# winderController02.net
KiCad netlist of a schematic drawn in EAGLE
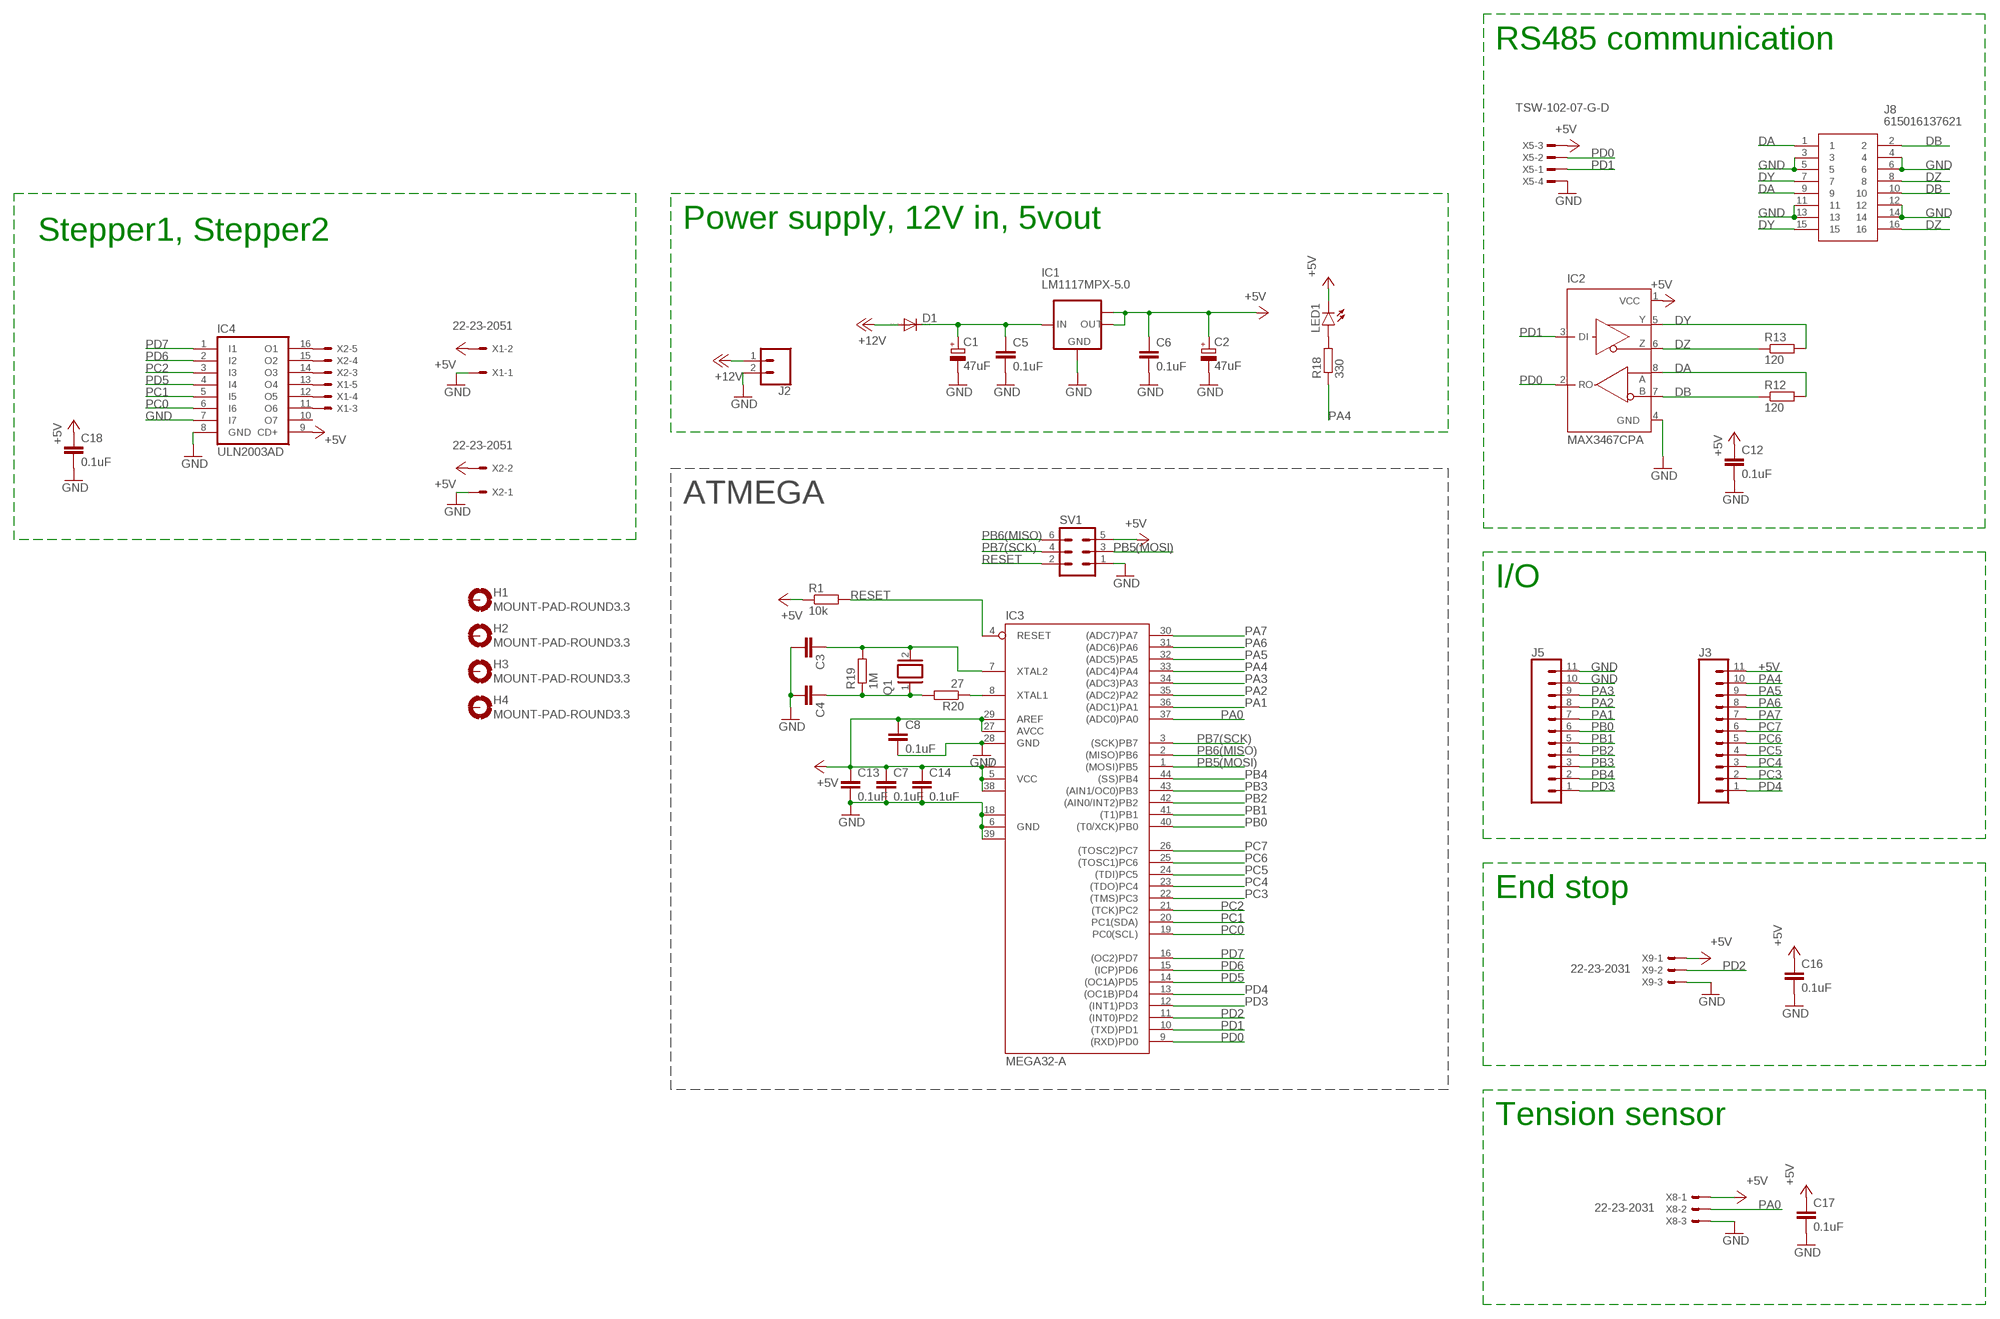
[diagram p0: schematic, sheet 1]

(export (version "E")
  (design (tool "Eeschema 10.0.6"))
  (components
    (comp (ref "C1")
      (value "47uF")
      (footprint "eagle-import:PANASONIC_D")
      (libsource (lib "eagle-import") (part "CPOL-EUD"))
    )
    (comp (ref "C2")
      (value "47uF")
      (footprint "eagle-import:PANASONIC_D")
      (libsource (lib "eagle-import") (part "CPOL-EUD"))
    )
    (comp (ref "C3")
      (value "C-EUC0603")
      (footprint "eagle-import:C0603")
      (libsource (lib "eagle-import") (part "C-EUC0603"))
    )
    (comp (ref "C4")
      (value "C-EUC0603")
      (footprint "eagle-import:C0603")
      (libsource (lib "eagle-import") (part "C-EUC0603"))
    )
    (comp (ref "C5")
      (value "0.1uF")
      (footprint "eagle-import:C0603")
      (libsource (lib "eagle-import") (part "C-EUC0603"))
    )
    (comp (ref "C6")
      (value "0.1uF")
      (footprint "eagle-import:C0603")
      (libsource (lib "eagle-import") (part "C-EUC0603"))
    )
    (comp (ref "C7")
      (value "0.1uF")
      (footprint "eagle-import:C0603")
      (libsource (lib "eagle-import") (part "C-EUC0603"))
    )
    (comp (ref "C8")
      (value "0.1uF")
      (footprint "eagle-import:C0603")
      (libsource (lib "eagle-import") (part "C-EUC0603"))
    )
    (comp (ref "C12")
      (value "0.1uF")
      (footprint "eagle-import:C0603")
      (libsource (lib "eagle-import") (part "C-EUC0603"))
    )
    (comp (ref "C13")
      (value "0.1uF")
      (footprint "eagle-import:C0603")
      (libsource (lib "eagle-import") (part "C-EUC0603"))
    )
    (comp (ref "C14")
      (value "0.1uF")
      (footprint "eagle-import:C0603")
      (libsource (lib "eagle-import") (part "C-EUC0603"))
    )
    (comp (ref "C16")
      (value "0.1uF")
      (footprint "eagle-import:C0603")
      (libsource (lib "eagle-import") (part "C-EUC0603"))
    )
    (comp (ref "C17")
      (value "0.1uF")
      (footprint "eagle-import:C0603")
      (libsource (lib "eagle-import") (part "C-EUC0603"))
    )
    (comp (ref "C18")
      (value "0.1uF")
      (footprint "eagle-import:C0603")
      (libsource (lib "eagle-import") (part "C-EUC0603"))
    )
    (comp (ref "D1")
      (value "DIODE-SMB")
      (footprint "eagle-import:SMB")
      (libsource (lib "eagle-import") (part "DIODE-SMB"))
    )
    (comp (ref "H1")
      (value "MOUNT-PAD-ROUND3.3")
      (footprint "eagle-import:3,3-PAD")
      (libsource (lib "eagle-import") (part "MOUNT-PAD-ROUND3.3"))
    )
    (comp (ref "H2")
      (value "MOUNT-PAD-ROUND3.3")
      (footprint "eagle-import:3,3-PAD")
      (libsource (lib "eagle-import") (part "MOUNT-PAD-ROUND3.3"))
    )
    (comp (ref "H3")
      (value "MOUNT-PAD-ROUND3.3")
      (footprint "eagle-import:3,3-PAD")
      (libsource (lib "eagle-import") (part "MOUNT-PAD-ROUND3.3"))
    )
    (comp (ref "H4")
      (value "MOUNT-PAD-ROUND3.3")
      (footprint "eagle-import:3,3-PAD")
      (libsource (lib "eagle-import") (part "MOUNT-PAD-ROUND3.3"))
    )
    (comp (ref "IC1")
      (value "LM1117MPX-5.0")
      (footprint "eagle-import:SOT223")
      (libsource (lib "eagle-import") (part "LM1117MPX-5.0"))
    )
    (comp (ref "IC2")
      (value "MAX3467CPA")
      (footprint "eagle-import:SO08")
      (libsource (lib "eagle-import") (part "MAX3467PAC"))
    )
    (comp (ref "IC3")
      (value "MEGA32-A")
      (footprint "eagle-import:TQFP44")
      (fields (field (name "MPN") "ATMEGA32-16AU"))
      (libsource (lib "eagle-import") (part "MEGA32-A"))
    )
    (comp (ref "IC4")
      (value "ULN2003AD")
      (footprint "eagle-import:SO16")
      (libsource (lib "eagle-import") (part "ULN2003AD"))
    )
    (comp (ref "J2")
      (value "CONN_023.5MM")
      (footprint "eagle-import:SCREWTERMINAL-3.5MM-2")
      (libsource (lib "eagle-import") (part "CONN_023.5MM"))
    )
    (comp (ref "J3")
      (value "CONN_11")
      (footprint "eagle-import:1X11")
      (libsource (lib "eagle-import") (part "CONN_11"))
    )
    (comp (ref "J5")
      (value "CONN_11")
      (footprint "eagle-import:1X11")
      (libsource (lib "eagle-import") (part "CONN_11"))
    )
    (comp (ref "J8")
      (value "615016137621")
      (footprint "eagle-import:WR-MJ")
      (fields (field (name "MOUSER_PART_NUMBER") "710-615016137621"))
      (libsource (lib "eagle-import") (part "615016137621"))
    )
    (comp (ref "LED1")
      (value "LEDSML1206")
      (footprint "eagle-import:SML1206")
      (libsource (lib "eagle-import") (part "LEDSML1206"))
    )
    (comp (ref "Q1")
      (value "XTAL/S")
      (footprint "eagle-import:QS")
      (fields (field (name "SPICEPREFIX") "B"))
      (libsource (lib "eagle-import") (part "XTAL/S"))
    )
    (comp (ref "R1")
      (value "10k")
      (footprint "eagle-import:R0805")
      (libsource (lib "eagle-import") (part "R-EU_R0805"))
    )
    (comp (ref "R12")
      (value "120")
      (footprint "eagle-import:R1210")
      (libsource (lib "eagle-import") (part "R-EU_R1210"))
    )
    (comp (ref "R13")
      (value "120")
      (footprint "eagle-import:R1210")
      (libsource (lib "eagle-import") (part "R-EU_R1210"))
    )
    (comp (ref "R18")
      (value "330")
      (footprint "eagle-import:R0805")
      (libsource (lib "eagle-import") (part "R-EU_R0805"))
    )
    (comp (ref "R19")
      (value "1M")
      (footprint "eagle-import:R0805")
      (libsource (lib "eagle-import") (part "R-EU_R0805"))
    )
    (comp (ref "R20")
      (value "27")
      (footprint "eagle-import:R0805")
      (libsource (lib "eagle-import") (part "R-EU_R0805"))
    )
    (comp (ref "SV1")
      (value "MA03-2")
      (footprint "eagle-import:MA03-2")
      (libsource (lib "eagle-import") (part "MA03-2"))
    )
    (comp (ref "X1")
      (value "22-23-2051")
      (footprint "eagle-import:22-23-2051")
      (fields (field (name "MF") "MOLEX"))
      (libsource (lib "eagle-import") (part "22-23-2051"))
    )
    (comp (ref "X2")
      (value "22-23-2051")
      (footprint "eagle-import:22-23-2051")
      (fields (field (name "MF") "MOLEX"))
      (libsource (lib "eagle-import") (part "22-23-2051"))
    )
    (comp (ref "X5")
      (value "TSW-102-07-G-D")
      (footprint "eagle-import:TSW-102-XX-G-D")
      (fields (field (name "MF") "Samtec Inc."))
      (libsource (lib "eagle-import") (part "TSW-102--G-D07"))
    )
    (comp (ref "X8")
      (value "22-23-2031")
      (footprint "eagle-import:22-23-2031")
      (fields (field (name "MF") "MOLEX"))
      (libsource (lib "eagle-import") (part "22-23-2031"))
    )
    (comp (ref "X9")
      (value "22-23-2031")
      (footprint "eagle-import:22-23-2031")
      (fields (field (name "MF") "MOLEX"))
      (libsource (lib "eagle-import") (part "22-23-2031"))
    )
  )
  (nets
    (net (code "1") (name "+5V") (class "Default")
      (node (ref "C12") (pin "1") (pinfunction "1_1") (pintype "passive"))
      (node (ref "C13") (pin "1") (pinfunction "1_1") (pintype "passive"))
      (node (ref "C14") (pin "1") (pinfunction "1_1") (pintype "passive"))
      (node (ref "C16") (pin "1") (pinfunction "1_1") (pintype "passive"))
      (node (ref "C17") (pin "1") (pinfunction "1_1") (pintype "passive"))
      (node (ref "C18") (pin "1") (pinfunction "1_1") (pintype "passive"))
      (node (ref "C2") (pin "+") (pinfunction "+_+") (pintype "passive"))
      (node (ref "C6") (pin "1") (pinfunction "1_1") (pintype "passive"))
      (node (ref "C7") (pin "1") (pinfunction "1_1") (pintype "passive"))
      (node (ref "C8") (pin "1") (pinfunction "1_1") (pintype "passive"))
      (node (ref "IC1") (pin "2") (pinfunction "OUT_2") (pintype "passive"))
      (node (ref "IC1") (pin "TAB") (pinfunction "OUT1_TAB") (pintype "passive"))
      (node (ref "IC2") (pin "1") (pinfunction "VCC_1") (pintype "power_in"))
      (node (ref "IC3") (pin "17") (pinfunction "VCC1_17") (pintype "power_in"))
      (node (ref "IC3") (pin "27") (pinfunction "AVCC_27") (pintype "power_in"))
      (node (ref "IC3") (pin "29") (pinfunction "AREF_29") (pintype "passive"))
      (node (ref "IC3") (pin "38") (pinfunction "VCC2_38") (pintype "power_in"))
      (node (ref "IC3") (pin "5") (pinfunction "VCC_5") (pintype "power_in"))
      (node (ref "IC4") (pin "9") (pinfunction "CD+_9") (pintype "passive"))
      (node (ref "J3") (pin "11") (pinfunction "11_11") (pintype "passive"))
      (node (ref "LED1") (pin "C") (pinfunction "C_C") (pintype "passive"))
      (node (ref "R1") (pin "1") (pinfunction "1_1") (pintype "passive"))
      (node (ref "SV1") (pin "5") (pinfunction "5_5") (pintype "passive"))
      (node (ref "X1") (pin "2") (pinfunction "S_2") (pintype "passive"))
      (node (ref "X2") (pin "2") (pinfunction "S_2") (pintype "passive"))
      (node (ref "X5") (pin "3") (pinfunction "1_3") (pintype "passive"))
      (node (ref "X8") (pin "1") (pinfunction "S_1") (pintype "passive"))
      (node (ref "X9") (pin "1") (pinfunction "S_1") (pintype "passive"))
    )
    (net (code "2") (name "+12V") (class "Default")
      (node (ref "D1") (pin "A") (pinfunction "A_A") (pintype "passive"))
      (node (ref "J2") (pin "1") (pinfunction "1_1") (pintype "passive"))
    )
    (net (code "3") (name "/DA") (class "Default")
      (node (ref "IC2") (pin "8") (pinfunction "A_8") (pintype "passive"))
      (node (ref "J8") (pin "1") (pinfunction "1_1") (pintype "bidirectional"))
      (node (ref "J8") (pin "9") (pinfunction "9_9") (pintype "bidirectional"))
      (node (ref "R12") (pin "2") (pinfunction "2_2") (pintype "passive"))
    )
    (net (code "4") (name "/DB") (class "Default")
      (node (ref "IC2") (pin "7") (pinfunction "B_7") (pintype "passive"))
      (node (ref "J8") (pin "10") (pinfunction "10_10") (pintype "bidirectional"))
      (node (ref "J8") (pin "2") (pinfunction "2_2") (pintype "bidirectional"))
      (node (ref "R12") (pin "1") (pinfunction "1_1") (pintype "passive"))
    )
    (net (code "5") (name "/DY") (class "Default")
      (node (ref "IC2") (pin "5") (pinfunction "Y_5") (pintype "passive"))
      (node (ref "J8") (pin "15") (pinfunction "15_15") (pintype "bidirectional"))
      (node (ref "J8") (pin "7") (pinfunction "7_7") (pintype "bidirectional"))
      (node (ref "R13") (pin "2") (pinfunction "2_2") (pintype "passive"))
    )
    (net (code "6") (name "/DZ") (class "Default")
      (node (ref "IC2") (pin "6") (pinfunction "Z_6") (pintype "passive"))
      (node (ref "J8") (pin "16") (pinfunction "16_16") (pintype "bidirectional"))
      (node (ref "J8") (pin "8") (pinfunction "8_8") (pintype "bidirectional"))
      (node (ref "R13") (pin "1") (pinfunction "1_1") (pintype "passive"))
    )
    (net (code "7") (name "/PA0") (class "Default")
      (node (ref "IC3") (pin "37") (pinfunction "(ADC0)PA0_37") (pintype "bidirectional"))
      (node (ref "X8") (pin "2") (pinfunction "S_2") (pintype "passive"))
    )
    (net (code "8") (name "/PA1") (class "Default")
      (node (ref "IC3") (pin "36") (pinfunction "(ADC1)PA1_36") (pintype "bidirectional"))
      (node (ref "J5") (pin "7") (pinfunction "7_7") (pintype "passive"))
    )
    (net (code "9") (name "/PA2") (class "Default")
      (node (ref "IC3") (pin "35") (pinfunction "(ADC2)PA2_35") (pintype "bidirectional"))
      (node (ref "J5") (pin "8") (pinfunction "8_8") (pintype "passive"))
    )
    (net (code "10") (name "/PA3") (class "Default")
      (node (ref "IC3") (pin "34") (pinfunction "(ADC3)PA3_34") (pintype "bidirectional"))
      (node (ref "J5") (pin "9") (pinfunction "9_9") (pintype "passive"))
    )
    (net (code "11") (name "/PA4") (class "Default")
      (node (ref "IC3") (pin "33") (pinfunction "(ADC4)PA4_33") (pintype "bidirectional"))
      (node (ref "J3") (pin "10") (pinfunction "10_10") (pintype "passive"))
      (node (ref "R18") (pin "1") (pinfunction "1_1") (pintype "passive"))
    )
    (net (code "12") (name "/PA5") (class "Default")
      (node (ref "IC3") (pin "32") (pinfunction "(ADC5)PA5_32") (pintype "bidirectional"))
      (node (ref "J3") (pin "9") (pinfunction "9_9") (pintype "passive"))
    )
    (net (code "13") (name "/PA6") (class "Default")
      (node (ref "IC3") (pin "31") (pinfunction "(ADC6)PA6_31") (pintype "bidirectional"))
      (node (ref "J3") (pin "8") (pinfunction "8_8") (pintype "passive"))
    )
    (net (code "14") (name "/PA7") (class "Default")
      (node (ref "IC3") (pin "30") (pinfunction "(ADC7)PA7_30") (pintype "bidirectional"))
      (node (ref "J3") (pin "7") (pinfunction "7_7") (pintype "passive"))
    )
    (net (code "15") (name "/PB0") (class "Default")
      (node (ref "IC3") (pin "40") (pinfunction "(T0/XCK)PB0_40") (pintype "bidirectional"))
      (node (ref "J5") (pin "6") (pinfunction "6_6") (pintype "passive"))
    )
    (net (code "16") (name "/PB1") (class "Default")
      (node (ref "IC3") (pin "41") (pinfunction "(T1)PB1_41") (pintype "bidirectional"))
      (node (ref "J5") (pin "5") (pinfunction "5_5") (pintype "passive"))
    )
    (net (code "17") (name "/PB2") (class "Default")
      (node (ref "IC3") (pin "42") (pinfunction "(AIN0/INT2)PB2_42") (pintype "bidirectional"))
      (node (ref "J5") (pin "4") (pinfunction "4_4") (pintype "passive"))
    )
    (net (code "18") (name "/PB3") (class "Default")
      (node (ref "IC3") (pin "43") (pinfunction "(AIN1/OC0)PB3_43") (pintype "bidirectional"))
      (node (ref "J5") (pin "3") (pinfunction "3_3") (pintype "passive"))
    )
    (net (code "19") (name "/PB4") (class "Default")
      (node (ref "IC3") (pin "44") (pinfunction "(SS)PB4_44") (pintype "bidirectional"))
      (node (ref "J5") (pin "2") (pinfunction "2_2") (pintype "passive"))
    )
    (net (code "20") (name "/PB5(MOSI)") (class "Default")
      (node (ref "IC3") (pin "1") (pinfunction "(MOSI)PB5_1") (pintype "bidirectional"))
      (node (ref "SV1") (pin "3") (pinfunction "3_3") (pintype "passive"))
    )
    (net (code "21") (name "/PB6(MISO)") (class "Default")
      (node (ref "IC3") (pin "2") (pinfunction "(MISO)PB6_2") (pintype "bidirectional"))
      (node (ref "SV1") (pin "6") (pinfunction "6_6") (pintype "passive"))
    )
    (net (code "22") (name "/PB7(SCK)") (class "Default")
      (node (ref "IC3") (pin "3") (pinfunction "(SCK)PB7_3") (pintype "bidirectional"))
      (node (ref "SV1") (pin "4") (pinfunction "4_4") (pintype "passive"))
    )
    (net (code "23") (name "/PC0") (class "Default")
      (node (ref "IC3") (pin "19") (pinfunction "PC0(SCL)_19") (pintype "bidirectional"))
      (node (ref "IC4") (pin "6") (pinfunction "I6_6") (pintype "input"))
    )
    (net (code "24") (name "/PC1") (class "Default")
      (node (ref "IC3") (pin "20") (pinfunction "PC1(SDA)_20") (pintype "bidirectional"))
      (node (ref "IC4") (pin "5") (pinfunction "I5_5") (pintype "input"))
    )
    (net (code "25") (name "/PC2") (class "Default")
      (node (ref "IC3") (pin "21") (pinfunction "(TCK)PC2_21") (pintype "bidirectional"))
      (node (ref "IC4") (pin "3") (pinfunction "I3_3") (pintype "input"))
    )
    (net (code "26") (name "/PC3") (class "Default")
      (node (ref "IC3") (pin "22") (pinfunction "(TMS)PC3_22") (pintype "bidirectional"))
      (node (ref "J3") (pin "2") (pinfunction "2_2") (pintype "passive"))
    )
    (net (code "27") (name "/PC4") (class "Default")
      (node (ref "IC3") (pin "23") (pinfunction "(TDO)PC4_23") (pintype "bidirectional"))
      (node (ref "J3") (pin "3") (pinfunction "3_3") (pintype "passive"))
    )
    (net (code "28") (name "/PC5") (class "Default")
      (node (ref "IC3") (pin "24") (pinfunction "(TDI)PC5_24") (pintype "bidirectional"))
      (node (ref "J3") (pin "4") (pinfunction "4_4") (pintype "passive"))
    )
    (net (code "29") (name "/PC6") (class "Default")
      (node (ref "IC3") (pin "25") (pinfunction "(TOSC1)PC6_25") (pintype "bidirectional"))
      (node (ref "J3") (pin "5") (pinfunction "5_5") (pintype "passive"))
    )
    (net (code "30") (name "/PC7") (class "Default")
      (node (ref "IC3") (pin "26") (pinfunction "(TOSC2)PC7_26") (pintype "bidirectional"))
      (node (ref "J3") (pin "6") (pinfunction "6_6") (pintype "passive"))
    )
    (net (code "31") (name "/PD0") (class "Default")
      (node (ref "IC2") (pin "2") (pinfunction "RO_2") (pintype "output"))
      (node (ref "IC3") (pin "9") (pinfunction "(RXD)PD0_9") (pintype "bidirectional"))
      (node (ref "X5") (pin "2") (pinfunction "1_2") (pintype "passive"))
    )
    (net (code "32") (name "/PD1") (class "Default")
      (node (ref "IC2") (pin "3") (pinfunction "DI_3") (pintype "input"))
      (node (ref "IC3") (pin "10") (pinfunction "(TXD)PD1_10") (pintype "bidirectional"))
      (node (ref "X5") (pin "1") (pinfunction "1_1") (pintype "passive"))
    )
    (net (code "33") (name "/PD2") (class "Default")
      (node (ref "IC3") (pin "11") (pinfunction "(INT0)PD2_11") (pintype "bidirectional"))
      (node (ref "X9") (pin "2") (pinfunction "S_2") (pintype "passive"))
    )
    (net (code "34") (name "/PD3") (class "Default")
      (node (ref "IC3") (pin "12") (pinfunction "(INT1)PD3_12") (pintype "bidirectional"))
      (node (ref "J5") (pin "1") (pinfunction "1_1") (pintype "passive"))
    )
    (net (code "35") (name "/PD4") (class "Default")
      (node (ref "IC3") (pin "13") (pinfunction "(OC1B)PD4_13") (pintype "bidirectional"))
      (node (ref "J3") (pin "1") (pinfunction "1_1") (pintype "passive"))
    )
    (net (code "36") (name "/PD5") (class "Default")
      (node (ref "IC3") (pin "14") (pinfunction "(OC1A)PD5_14") (pintype "bidirectional"))
      (node (ref "IC4") (pin "4") (pinfunction "I4_4") (pintype "input"))
    )
    (net (code "37") (name "/PD6") (class "Default")
      (node (ref "IC3") (pin "15") (pinfunction "(ICP)PD6_15") (pintype "bidirectional"))
      (node (ref "IC4") (pin "2") (pinfunction "I2_2") (pintype "input"))
    )
    (net (code "38") (name "/PD7") (class "Default")
      (node (ref "IC3") (pin "16") (pinfunction "(OC2)PD7_16") (pintype "bidirectional"))
      (node (ref "IC4") (pin "1") (pinfunction "I1_1") (pintype "input"))
    )
    (net (code "39") (name "/RESET") (class "Default")
      (node (ref "IC3") (pin "4") (pinfunction "RESET_4") (pintype "input"))
      (node (ref "R1") (pin "2") (pinfunction "2_2") (pintype "passive"))
      (node (ref "SV1") (pin "2") (pinfunction "2_2") (pintype "passive"))
    )
    (net (code "40") (name "GND") (class "Default")
      (node (ref "C1") (pin "-") (pinfunction "-_-") (pintype "passive"))
      (node (ref "C12") (pin "2") (pinfunction "2_2") (pintype "passive"))
      (node (ref "C13") (pin "2") (pinfunction "2_2") (pintype "passive"))
      (node (ref "C14") (pin "2") (pinfunction "2_2") (pintype "passive"))
      (node (ref "C16") (pin "2") (pinfunction "2_2") (pintype "passive"))
      (node (ref "C17") (pin "2") (pinfunction "2_2") (pintype "passive"))
      (node (ref "C18") (pin "2") (pinfunction "2_2") (pintype "passive"))
      (node (ref "C2") (pin "-") (pinfunction "-_-") (pintype "passive"))
      (node (ref "C3") (pin "2") (pinfunction "2_2") (pintype "passive"))
      (node (ref "C4") (pin "2") (pinfunction "2_2") (pintype "passive"))
      (node (ref "C5") (pin "2") (pinfunction "2_2") (pintype "passive"))
      (node (ref "C6") (pin "2") (pinfunction "2_2") (pintype "passive"))
      (node (ref "C7") (pin "2") (pinfunction "2_2") (pintype "passive"))
      (node (ref "C8") (pin "2") (pinfunction "2_2") (pintype "passive"))
      (node (ref "IC1") (pin "1") (pinfunction "GND_1") (pintype "input"))
      (node (ref "IC2") (pin "4") (pinfunction "GND_4") (pintype "power_in"))
      (node (ref "IC3") (pin "18") (pinfunction "GND1_18") (pintype "power_in"))
      (node (ref "IC3") (pin "28") (pinfunction "GND_28") (pintype "power_in"))
      (node (ref "IC3") (pin "39") (pinfunction "GND2_39") (pintype "power_in"))
      (node (ref "IC3") (pin "6") (pinfunction "GND_6") (pintype "power_in"))
      (node (ref "IC4") (pin "7") (pinfunction "I7_7") (pintype "input"))
      (node (ref "IC4") (pin "8") (pinfunction "GND_8") (pintype "power_in"))
      (node (ref "J2") (pin "2") (pinfunction "2_2") (pintype "passive"))
      (node (ref "J5") (pin "10") (pinfunction "10_10") (pintype "passive"))
      (node (ref "J5") (pin "11") (pinfunction "11_11") (pintype "passive"))
      (node (ref "J8") (pin "11") (pinfunction "11_11") (pintype "bidirectional"))
      (node (ref "J8") (pin "12") (pinfunction "12_12") (pintype "bidirectional"))
      (node (ref "J8") (pin "13") (pinfunction "13_13") (pintype "bidirectional"))
      (node (ref "J8") (pin "14") (pinfunction "14_14") (pintype "bidirectional"))
      (node (ref "J8") (pin "3") (pinfunction "3_3") (pintype "bidirectional"))
      (node (ref "J8") (pin "4") (pinfunction "4_4") (pintype "bidirectional"))
      (node (ref "J8") (pin "5") (pinfunction "5_5") (pintype "bidirectional"))
      (node (ref "J8") (pin "6") (pinfunction "6_6") (pintype "bidirectional"))
      (node (ref "SV1") (pin "1") (pinfunction "1_1") (pintype "passive"))
      (node (ref "X1") (pin "1") (pinfunction "S_1") (pintype "passive"))
      (node (ref "X2") (pin "1") (pinfunction "S_1") (pintype "passive"))
      (node (ref "X5") (pin "4") (pinfunction "1_4") (pintype "passive"))
      (node (ref "X8") (pin "3") (pinfunction "S_3") (pintype "passive"))
      (node (ref "X9") (pin "3") (pinfunction "S_3") (pintype "passive"))
    )
    (net (code "41") (name "Net-(C4-Pad1)") (class "Default")
      (node (ref "C4") (pin "1") (pinfunction "1_1") (pintype "passive"))
      (node (ref "Q1") (pin "1") (pinfunction "1_1") (pintype "passive"))
      (node (ref "R19") (pin "1") (pinfunction "1_1") (pintype "passive"))
      (node (ref "R20") (pin "2") (pinfunction "2_2") (pintype "passive"))
    )
    (net (code "42") (name "Net-(IC1-IN)") (class "Default")
      (node (ref "C1") (pin "+") (pinfunction "+_+") (pintype "passive"))
      (node (ref "C5") (pin "1") (pinfunction "1_1") (pintype "passive"))
      (node (ref "D1") (pin "C") (pinfunction "C_C") (pintype "passive"))
      (node (ref "IC1") (pin "3") (pinfunction "IN_3") (pintype "input"))
    )
    (net (code "43") (name "Net-(IC3-XTAL1)") (class "Default")
      (node (ref "IC3") (pin "8") (pinfunction "XTAL1_8") (pintype "bidirectional"))
      (node (ref "R20") (pin "1") (pinfunction "1_1") (pintype "passive"))
    )
    (net (code "44") (name "Net-(IC3-XTAL2)") (class "Default")
      (node (ref "C3") (pin "1") (pinfunction "1_1") (pintype "passive"))
      (node (ref "IC3") (pin "7") (pinfunction "XTAL2_7") (pintype "bidirectional"))
      (node (ref "Q1") (pin "2") (pinfunction "2_2") (pintype "passive"))
      (node (ref "R19") (pin "2") (pinfunction "2_2") (pintype "passive"))
    )
    (net (code "45") (name "Net-(IC4-O1)") (class "Default")
      (node (ref "IC4") (pin "16") (pinfunction "O1_16") (pintype "open_collector"))
      (node (ref "X2") (pin "5") (pinfunction "S_5") (pintype "passive"))
    )
    (net (code "46") (name "Net-(IC4-O2)") (class "Default")
      (node (ref "IC4") (pin "15") (pinfunction "O2_15") (pintype "open_collector"))
      (node (ref "X2") (pin "4") (pinfunction "S_4") (pintype "passive"))
    )
    (net (code "47") (name "Net-(IC4-O3)") (class "Default")
      (node (ref "IC4") (pin "14") (pinfunction "O3_14") (pintype "open_collector"))
      (node (ref "X2") (pin "3") (pinfunction "S_3") (pintype "passive"))
    )
    (net (code "48") (name "Net-(IC4-O4)") (class "Default")
      (node (ref "IC4") (pin "13") (pinfunction "O4_13") (pintype "open_collector"))
      (node (ref "X1") (pin "5") (pinfunction "S_5") (pintype "passive"))
    )
    (net (code "49") (name "Net-(IC4-O5)") (class "Default")
      (node (ref "IC4") (pin "12") (pinfunction "O5_12") (pintype "open_collector"))
      (node (ref "X1") (pin "4") (pinfunction "S_4") (pintype "passive"))
    )
    (net (code "50") (name "Net-(IC4-O6)") (class "Default")
      (node (ref "IC4") (pin "11") (pinfunction "O6_11") (pintype "open_collector"))
      (node (ref "X1") (pin "3") (pinfunction "S_3") (pintype "passive"))
    )
    (net (code "51") (name "Net-(LED1-PadA)") (class "Default")
      (node (ref "LED1") (pin "A") (pinfunction "A_A") (pintype "passive"))
      (node (ref "R18") (pin "2") (pinfunction "2_2") (pintype "passive"))
    )
    (net (code "52") (name "unconnected-(H1-MOUNT-PadB3,3)") (class "Default")
      (node (ref "H1") (pin "B3,3") (pinfunction "MOUNT_B3,3") (pintype "passive"))
    )
    (net (code "53") (name "unconnected-(H2-MOUNT-PadB3,3)") (class "Default")
      (node (ref "H2") (pin "B3,3") (pinfunction "MOUNT_B3,3") (pintype "passive"))
    )
    (net (code "54") (name "unconnected-(H3-MOUNT-PadB3,3)") (class "Default")
      (node (ref "H3") (pin "B3,3") (pinfunction "MOUNT_B3,3") (pintype "passive"))
    )
    (net (code "55") (name "unconnected-(H4-MOUNT-PadB3,3)") (class "Default")
      (node (ref "H4") (pin "B3,3") (pinfunction "MOUNT_B3,3") (pintype "passive"))
    )
    (net (code "56") (name "unconnected-(IC4-O7-Pad10)") (class "Default")
      (node (ref "IC4") (pin "10") (pinfunction "O7_10") (pintype "open_collector"))
    )
  )
)
